# RC_Sheet1.net
KiCad netlist of a schematic drawn in Altium Designer
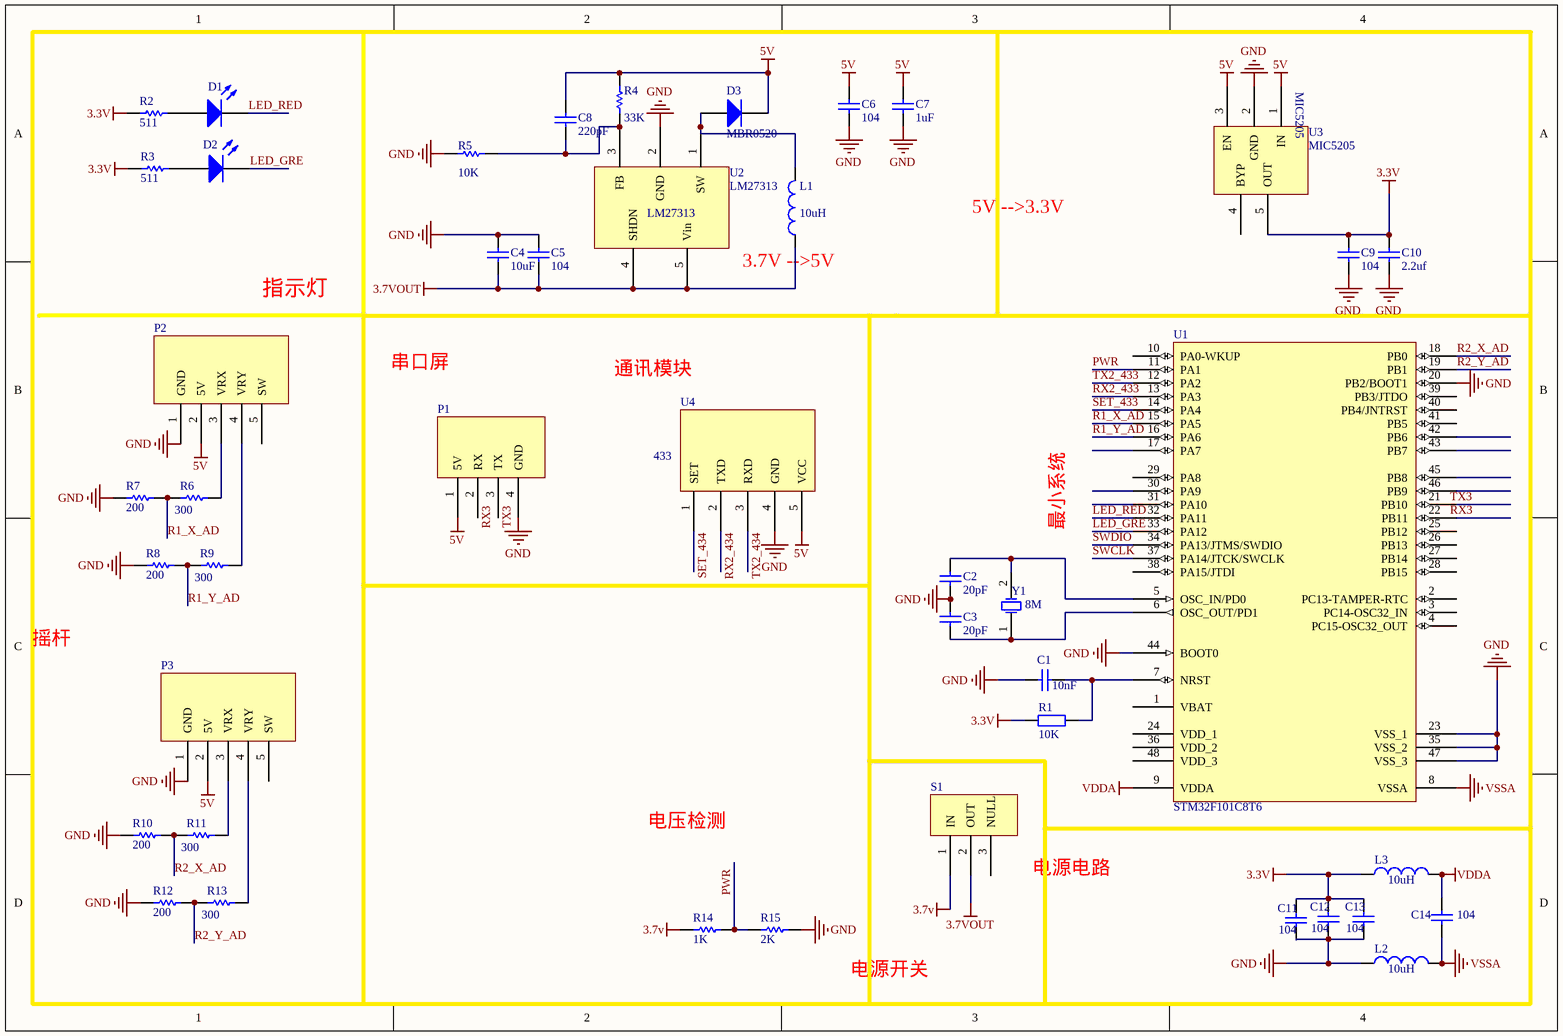
[diagram p0: RC_Sheet1.SchDoc]

(export (version "E")
  (design (tool "Eeschema 10.0.6"))
  (components
    (comp (ref "C1")
      (value "10nF")
      (footprint "0603-N-CAP")
      (description "Capacitor")
      (fields (field (name "Comment") "Cap") (field (name "PUBLISHER") "Altium Limited"))
      (libsource (lib "Miscellaneous Devices") (part "Cap"))
    )
    (comp (ref "C2")
      (value "20pF")
      (footprint "0603-N-CAP")
      (description "Capacitor")
      (fields (field (name "Comment") "Cap") (field (name "PUBLISHER") "Altium Limited"))
      (libsource (lib "Miscellaneous Devices") (part "Cap"))
    )
    (comp (ref "C3")
      (value "20pF")
      (footprint "0603-N-CAP")
      (description "Capacitor")
      (fields (field (name "Comment") "Cap") (field (name "PUBLISHER") "Altium Limited"))
      (libsource (lib "Miscellaneous Devices") (part "Cap"))
    )
    (comp (ref "C4")
      (value "10uF")
      (footprint "0603-N-CAP")
      (description "Capacitor")
      (fields (field (name "Comment") "Cap") (field (name "PUBLISHER") "Altium Limited"))
      (libsource (lib "Miscellaneous Devices") (part "Cap"))
    )
    (comp (ref "C5")
      (value "104")
      (footprint "0603-N-CAP")
      (description "Capacitor")
      (fields (field (name "Comment") "Cap") (field (name "PUBLISHER") "Altium Limited"))
      (libsource (lib "Miscellaneous Devices") (part "Cap"))
    )
    (comp (ref "C6")
      (value "104")
      (footprint "0603-N-CAP")
      (description "Capacitor")
      (fields (field (name "Comment") "Cap") (field (name "PUBLISHER") "Altium Limited"))
      (libsource (lib "Miscellaneous Devices") (part "Cap"))
    )
    (comp (ref "C7")
      (value "1uF")
      (footprint "0603-N-CAP")
      (description "Capacitor")
      (fields (field (name "Comment") "Cap") (field (name "PUBLISHER") "Altium Limited"))
      (libsource (lib "Miscellaneous Devices") (part "Cap"))
    )
    (comp (ref "C8")
      (value "220pF")
      (footprint "0603-N-CAP")
      (description "Capacitor")
      (fields (field (name "Comment") "Cap") (field (name "PUBLISHER") "Altium Limited"))
      (libsource (lib "Miscellaneous Devices") (part "Cap"))
    )
    (comp (ref "C9")
      (value "104")
      (footprint "0603-N-CAP")
      (description "Capacitor")
      (fields (field (name "Comment") "Cap") (field (name "PUBLISHER") "Altium Limited"))
      (libsource (lib "Miscellaneous Devices") (part "Cap"))
    )
    (comp (ref "C10")
      (value "2.2uf")
      (footprint "0603-N-CAP")
      (description "Capacitor")
      (fields (field (name "Comment") "Cap") (field (name "PUBLISHER") "Altium Limited"))
      (libsource (lib "Miscellaneous Devices") (part "Cap"))
    )
    (comp (ref "C11")
      (value "104")
      (footprint "0603-N-CAP")
      (description "Capacitor")
      (fields (field (name "Comment") "Cap") (field (name "PUBLISHER") "Altium Limited"))
      (libsource (lib "Miscellaneous Devices") (part "Cap"))
    )
    (comp (ref "C12")
      (value "104")
      (footprint "0603-N-CAP")
      (description "Capacitor")
      (fields (field (name "Comment") "Cap") (field (name "PUBLISHER") "Altium Limited"))
      (libsource (lib "Miscellaneous Devices") (part "Cap"))
    )
    (comp (ref "C13")
      (value "104")
      (footprint "0603-N-CAP")
      (description "Capacitor")
      (fields (field (name "Comment") "Cap") (field (name "PUBLISHER") "Altium Limited"))
      (libsource (lib "Miscellaneous Devices") (part "Cap"))
    )
    (comp (ref "C14")
      (value "104")
      (footprint "0603-N-CAP")
      (description "Capacitor")
      (fields (field (name "Comment") "Cap") (field (name "PUBLISHER") "Altium Limited"))
      (libsource (lib "Miscellaneous Devices") (part "Cap"))
    )
    (comp (ref "D1")
      (value "D2")
      (footprint "0603-N - LED-RED")
      (description "Typical BLUE SiC LED")
      (fields (field (name "PUBLISHER") "Altium Limited"))
      (libsource (lib "Miscellaneous Devices") (part "LED3"))
    )
    (comp (ref "D2")
      (value "D2")
      (footprint "0603-N - LED-RED")
      (description "Typical BLUE SiC LED")
      (fields (field (name "PUBLISHER") "Altium Limited"))
      (libsource (lib "Miscellaneous Devices") (part "LED3"))
    )
    (comp (ref "D3")
      (value "MBR0520")
      (footprint "425")
      (description "Default Diode")
      (fields (field (name "PUBLISHER") "Altium Limited"))
      (libsource (lib "Miscellaneous Devices") (part "Diode"))
    )
    (comp (ref "L1")
      (value "10uH")
      (footprint "0603-N - res")
      (description "Inductor")
      (fields (field (name "PUBLISHER") "Altium Limited"))
      (libsource (lib "Miscellaneous Devices") (part "Inductor"))
    )
    (comp (ref "L2")
      (value "10uH")
      (footprint "0603-N - res")
      (description "Inductor")
      (fields (field (name "PUBLISHER") "Altium Limited"))
      (libsource (lib "Miscellaneous Devices") (part "Inductor"))
    )
    (comp (ref "L3")
      (value "10uH")
      (footprint "0603-N - res")
      (description "Inductor")
      (fields (field (name "PUBLISHER") "Altium Limited"))
      (libsource (lib "Miscellaneous Devices") (part "Inductor"))
    )
    (comp (ref "P1") (value "串口屏") (libsource (lib "Schlib1") (part "串口屏")))
    (comp (ref "P2") (value "手柄") (libsource (lib "Schlib1") (part "手柄")))
    (comp (ref "P3") (value "手柄") (libsource (lib "Schlib1") (part "手柄")))
    (comp (ref "R1")
      (value "10K")
      (footprint "0603-N - res")
      (description "Resistor")
      (fields (field (name "Comment") "Res2") (field (name "PUBLISHER") "Altium Limited"))
      (libsource (lib "Miscellaneous Devices") (part "Res2"))
    )
    (comp (ref "R2")
      (value "511")
      (footprint "0603-N - res")
      (description "Resistor")
      (fields (field (name "Comment") "Res1") (field (name "PUBLISHER") "Altium Limited"))
      (libsource (lib "Miscellaneous Devices") (part "Res1"))
    )
    (comp (ref "R3")
      (value "511")
      (footprint "0603-N - res")
      (description "Resistor")
      (fields (field (name "Comment") "Res1") (field (name "PUBLISHER") "Altium Limited"))
      (libsource (lib "Miscellaneous Devices") (part "Res1"))
    )
    (comp (ref "R4")
      (value "33K")
      (footprint "0603-N - res")
      (description "Resistor")
      (fields (field (name "Comment") "Res1") (field (name "PUBLISHER") "Altium Limited"))
      (libsource (lib "Miscellaneous Devices") (part "Res1"))
    )
    (comp (ref "R5")
      (value "10K")
      (footprint "0603-N - res")
      (description "Resistor")
      (fields (field (name "Comment") "Res1") (field (name "PUBLISHER") "Altium Limited"))
      (libsource (lib "Miscellaneous Devices") (part "Res1"))
    )
    (comp (ref "R6")
      (value "300")
      (footprint "0603-N - res")
      (description "Resistor")
      (fields (field (name "Comment") "Res1") (field (name "PUBLISHER") "Altium Limited"))
      (libsource (lib "Miscellaneous Devices") (part "Res1"))
    )
    (comp (ref "R7")
      (value "200")
      (footprint "0603-N - res")
      (description "Resistor")
      (fields (field (name "Comment") "Res1") (field (name "PUBLISHER") "Altium Limited"))
      (libsource (lib "Miscellaneous Devices") (part "Res1"))
    )
    (comp (ref "R8")
      (value "200")
      (footprint "0603-N - res")
      (description "Resistor")
      (fields (field (name "Comment") "Res1") (field (name "PUBLISHER") "Altium Limited"))
      (libsource (lib "Miscellaneous Devices") (part "Res1"))
    )
    (comp (ref "R9")
      (value "300")
      (footprint "0603-N - res")
      (description "Resistor")
      (fields (field (name "Comment") "Res1") (field (name "PUBLISHER") "Altium Limited"))
      (libsource (lib "Miscellaneous Devices") (part "Res1"))
    )
    (comp (ref "R10")
      (value "200")
      (footprint "0603-N - res")
      (description "Resistor")
      (fields (field (name "Comment") "Res1") (field (name "PUBLISHER") "Altium Limited"))
      (libsource (lib "Miscellaneous Devices") (part "Res1"))
    )
    (comp (ref "R11")
      (value "300")
      (footprint "0603-N - res")
      (description "Resistor")
      (fields (field (name "Comment") "Res1") (field (name "PUBLISHER") "Altium Limited"))
      (libsource (lib "Miscellaneous Devices") (part "Res1"))
    )
    (comp (ref "R12")
      (value "200")
      (footprint "0603-N - res")
      (description "Resistor")
      (fields (field (name "Comment") "Res1") (field (name "PUBLISHER") "Altium Limited"))
      (libsource (lib "Miscellaneous Devices") (part "Res1"))
    )
    (comp (ref "R13")
      (value "300")
      (footprint "0603-N - res")
      (description "Resistor")
      (fields (field (name "Comment") "Res1") (field (name "PUBLISHER") "Altium Limited"))
      (libsource (lib "Miscellaneous Devices") (part "Res1"))
    )
    (comp (ref "R14")
      (value "1K")
      (footprint "0603-N - res")
      (description "Resistor")
      (fields (field (name "Comment") "Res1") (field (name "PUBLISHER") "Altium Limited"))
      (libsource (lib "Miscellaneous Devices") (part "Res1"))
    )
    (comp (ref "R15")
      (value "2K")
      (footprint "0603-N - res")
      (description "Resistor")
      (fields (field (name "Comment") "Res1") (field (name "PUBLISHER") "Altium Limited"))
      (libsource (lib "Miscellaneous Devices") (part "Res1"))
    )
    (comp (ref "S1") (value "switch") (footprint "SWITCH") (libsource (lib "Schlib1") (part "switch")))
    (comp (ref "U1")
      (value "STM32F101C8T6")
      (footprint "LQFP48_N")
      (description "STM32 ARM-based 32-bit MCU with 64 Kbytes Flash, 48-pin LQFP, Industrial Temperature")
      (fields (field (name "PUBLISHER") "Altium Limited"))
      (libsource (lib "ST Microcontroller 32-Bit STM32") (part "STM32F101C8T6"))
    )
    (comp (ref "U2")
      (value "LM27313")
      (footprint "SOT-23_5-001")
      (description "3.7V升压到5v")
      (libsource (lib "Schlib1") (part "LM27313"))
    )
    (comp (ref "U3")
      (value "MIC5205")
      (footprint "SOT-23_5-001")
      (description "5V降压到3.3V")
      (libsource (lib "Schlib1") (part "MIC5205"))
    )
    (comp (ref "U4")
      (value "433")
      (footprint "433")
      (description "通讯模块")
      (libsource (lib "Schlib1") (part "433"))
    )
    (comp (ref "Y1")
      (value "8M")
      (footprint "5032_")
      (description "Crystal Oscillator")
      (fields (field (name "PUBLISHER") "Altium Limited"))
      (libsource (lib "Miscellaneous Devices") (part "XTAL"))
    )
  )
  (nets
    (net (code "1") (name "/LED_GRE") (class "Default")
      (node (ref "D2") (pin "2") (pinfunction "K_2") (pintype "passive"))
      (node (ref "U1") (pin "33") (pinfunction "PA12_33") (pintype "bidirectional"))
    )
    (net (code "2") (name "/LED_RED") (class "Default")
      (node (ref "D1") (pin "2") (pinfunction "K_2") (pintype "passive"))
      (node (ref "U1") (pin "32") (pinfunction "PA11_32") (pintype "bidirectional"))
    )
    (net (code "3") (name "/PWR") (class "Default")
      (node (ref "R14") (pin "2") (pinfunction "2_2") (pintype "passive"))
      (node (ref "R15") (pin "1") (pinfunction "1_1") (pintype "passive"))
      (node (ref "U1") (pin "11") (pinfunction "PA1_11") (pintype "bidirectional"))
    )
    (net (code "4") (name "/R1_X_AD") (class "Default")
      (node (ref "R6") (pin "2") (pinfunction "2_2") (pintype "passive"))
      (node (ref "R7") (pin "1") (pinfunction "1_1") (pintype "passive"))
      (node (ref "U1") (pin "15") (pinfunction "PA5_15") (pintype "bidirectional"))
    )
    (net (code "5") (name "/R1_Y_AD") (class "Default")
      (node (ref "R8") (pin "1") (pinfunction "1_1") (pintype "passive"))
      (node (ref "R9") (pin "2") (pinfunction "2_2") (pintype "passive"))
      (node (ref "U1") (pin "16") (pinfunction "PA6_16") (pintype "bidirectional"))
    )
    (net (code "6") (name "/R2_X_AD") (class "Default")
      (node (ref "R10") (pin "1") (pinfunction "1_1") (pintype "passive"))
      (node (ref "R11") (pin "2") (pinfunction "2_2") (pintype "passive"))
      (node (ref "U1") (pin "18") (pinfunction "PB0_18") (pintype "bidirectional"))
    )
    (net (code "7") (name "/R2_Y_AD") (class "Default")
      (node (ref "R12") (pin "1") (pinfunction "1_1") (pintype "passive"))
      (node (ref "R13") (pin "2") (pinfunction "2_2") (pintype "passive"))
      (node (ref "U1") (pin "19") (pinfunction "PB1_19") (pintype "bidirectional"))
    )
    (net (code "8") (name "/RX2_433") (class "Default")
      (node (ref "U1") (pin "13") (pinfunction "PA3_13") (pintype "bidirectional"))
    )
    (net (code "9") (name "/RX2_434") (class "Default")
      (node (ref "U4") (pin "2") (pinfunction "TXD_2") (pintype "passive"))
    )
    (net (code "11") (name "/SET_433") (class "Default")
      (node (ref "U1") (pin "14") (pinfunction "PA4_14") (pintype "bidirectional"))
    )
    (net (code "12") (name "/SET_434") (class "Default")
      (node (ref "U4") (pin "1") (pinfunction "SET_1") (pintype "passive"))
    )
    (net (code "13") (name "/SWCLK") (class "Default")
      (node (ref "U1") (pin "37") (pinfunction "PA14/JTCK/SWCLK_37") (pintype "bidirectional"))
    )
    (net (code "14") (name "/SWDIO") (class "Default")
      (node (ref "U1") (pin "34") (pinfunction "PA13/JTMS/SWDIO_34") (pintype "bidirectional"))
    )
    (net (code "15") (name "/TX2_433") (class "Default")
      (node (ref "U1") (pin "12") (pinfunction "PA2_12") (pintype "bidirectional"))
    )
    (net (code "16") (name "/TX2_434") (class "Default")
      (node (ref "U4") (pin "3") (pinfunction "RXD_3") (pintype "passive"))
    )
    (net (code "18") (name "3.3V") (class "Default")
      (node (ref "C10") (pin "2") (pinfunction "2_2") (pintype "passive"))
      (node (ref "C11") (pin "2") (pinfunction "2_2") (pintype "passive"))
      (node (ref "C12") (pin "2") (pinfunction "2_2") (pintype "passive"))
      (node (ref "C13") (pin "2") (pinfunction "2_2") (pintype "passive"))
      (node (ref "C9") (pin "2") (pinfunction "2_2") (pintype "passive"))
      (node (ref "L3") (pin "1") (pinfunction "1_1") (pintype "passive"))
      (node (ref "R1") (pin "1") (pinfunction "1_1") (pintype "passive"))
      (node (ref "R2") (pin "2") (pinfunction "2_2") (pintype "passive"))
      (node (ref "R3") (pin "2") (pinfunction "2_2") (pintype "passive"))
      (node (ref "U3") (pin "5") (pinfunction "OUT_5") (pintype "passive"))
    )
    (net (code "19") (name "3.7VOUT") (class "Default")
      (node (ref "C4") (pin "1") (pinfunction "1_1") (pintype "passive"))
      (node (ref "C5") (pin "1") (pinfunction "1_1") (pintype "passive"))
      (node (ref "L1") (pin "1") (pinfunction "1_1") (pintype "passive"))
      (node (ref "S1") (pin "2") (pinfunction "OUT_2") (pintype "passive"))
      (node (ref "U2") (pin "4") (pinfunction "SHDN_4") (pintype "passive"))
      (node (ref "U2") (pin "5") (pinfunction "Vin_5") (pintype "passive"))
    )
    (net (code "20") (name "3.7v") (class "Default")
      (node (ref "R14") (pin "1") (pinfunction "1_1") (pintype "passive"))
      (node (ref "S1") (pin "1") (pinfunction "IN_1") (pintype "passive"))
    )
    (net (code "21") (name "5V") (class "Default")
      (node (ref "C6") (pin "2") (pinfunction "2_2") (pintype "passive"))
      (node (ref "C7") (pin "2") (pinfunction "2_2") (pintype "passive"))
      (node (ref "C8") (pin "2") (pinfunction "2_2") (pintype "passive"))
      (node (ref "D3") (pin "2") (pinfunction "K_2") (pintype "passive"))
      (node (ref "P1") (pin "1") (pinfunction "5V_1") (pintype "passive"))
      (node (ref "P2") (pin "2") (pinfunction "5V_2") (pintype "passive"))
      (node (ref "P3") (pin "2") (pinfunction "5V_2") (pintype "passive"))
      (node (ref "R4") (pin "2") (pinfunction "2_2") (pintype "passive"))
      (node (ref "U3") (pin "1") (pinfunction "IN_1") (pintype "passive"))
      (node (ref "U3") (pin "3") (pinfunction "EN_3") (pintype "passive"))
      (node (ref "U4") (pin "5") (pinfunction "VCC_5") (pintype "passive"))
    )
    (net (code "22") (name "GND") (class "Default")
      (node (ref "C1") (pin "1") (pinfunction "1_1") (pintype "passive"))
      (node (ref "C10") (pin "1") (pinfunction "1_1") (pintype "passive"))
      (node (ref "C11") (pin "1") (pinfunction "1_1") (pintype "passive"))
      (node (ref "C12") (pin "1") (pinfunction "1_1") (pintype "passive"))
      (node (ref "C13") (pin "1") (pinfunction "1_1") (pintype "passive"))
      (node (ref "C2") (pin "1") (pinfunction "1_1") (pintype "passive"))
      (node (ref "C3") (pin "2") (pinfunction "2_2") (pintype "passive"))
      (node (ref "C4") (pin "2") (pinfunction "2_2") (pintype "passive"))
      (node (ref "C5") (pin "2") (pinfunction "2_2") (pintype "passive"))
      (node (ref "C6") (pin "1") (pinfunction "1_1") (pintype "passive"))
      (node (ref "C7") (pin "1") (pinfunction "1_1") (pintype "passive"))
      (node (ref "C9") (pin "1") (pinfunction "1_1") (pintype "passive"))
      (node (ref "L2") (pin "1") (pinfunction "1_1") (pintype "passive"))
      (node (ref "P1") (pin "4") (pinfunction "GND_4") (pintype "passive"))
      (node (ref "P2") (pin "1") (pinfunction "GND_1") (pintype "passive"))
      (node (ref "P3") (pin "1") (pinfunction "GND_1") (pintype "passive"))
      (node (ref "R10") (pin "2") (pinfunction "2_2") (pintype "passive"))
      (node (ref "R12") (pin "2") (pinfunction "2_2") (pintype "passive"))
      (node (ref "R15") (pin "2") (pinfunction "2_2") (pintype "passive"))
      (node (ref "R5") (pin "1") (pinfunction "1_1") (pintype "passive"))
      (node (ref "R7") (pin "2") (pinfunction "2_2") (pintype "passive"))
      (node (ref "R8") (pin "2") (pinfunction "2_2") (pintype "passive"))
      (node (ref "U1") (pin "20") (pinfunction "PB2/BOOT1_20") (pintype "bidirectional"))
      (node (ref "U1") (pin "23") (pinfunction "VSS_1_23") (pintype "power_in"))
      (node (ref "U1") (pin "35") (pinfunction "VSS_2_35") (pintype "power_in"))
      (node (ref "U1") (pin "44") (pinfunction "BOOT0_44") (pintype "input"))
      (node (ref "U1") (pin "47") (pinfunction "VSS_3_47") (pintype "power_in"))
      (node (ref "U2") (pin "2") (pinfunction "GND_2") (pintype "passive"))
      (node (ref "U3") (pin "2") (pinfunction "GND_2") (pintype "passive"))
      (node (ref "U4") (pin "4") (pinfunction "GND_4") (pintype "passive"))
    )
    (net (code "23") (name "Net-(D1-A)") (class "Default")
      (node (ref "D1") (pin "1") (pinfunction "A_1") (pintype "passive"))
      (node (ref "R2") (pin "1") (pinfunction "1_1") (pintype "passive"))
    )
    (net (code "24") (name "Net-(D2-A)") (class "Default")
      (node (ref "D2") (pin "1") (pinfunction "A_1") (pintype "passive"))
      (node (ref "R3") (pin "1") (pinfunction "1_1") (pintype "passive"))
    )
    (net (code "25") (name "Net-(D3-A)") (class "Default")
      (node (ref "D3") (pin "1") (pinfunction "A_1") (pintype "passive"))
      (node (ref "L1") (pin "2") (pinfunction "2_2") (pintype "passive"))
      (node (ref "U2") (pin "1") (pinfunction "SW_1") (pintype "passive"))
    )
    (net (code "26") (name "Net-(P2-VRX)") (class "Default")
      (node (ref "P2") (pin "3") (pinfunction "VRX_3") (pintype "passive"))
      (node (ref "R6") (pin "1") (pinfunction "1_1") (pintype "passive"))
    )
    (net (code "27") (name "Net-(P2-VRY)") (class "Default")
      (node (ref "P2") (pin "4") (pinfunction "VRY_4") (pintype "passive"))
      (node (ref "R9") (pin "1") (pinfunction "1_1") (pintype "passive"))
    )
    (net (code "28") (name "Net-(P3-VRX)") (class "Default")
      (node (ref "P3") (pin "3") (pinfunction "VRX_3") (pintype "passive"))
      (node (ref "R11") (pin "1") (pinfunction "1_1") (pintype "passive"))
    )
    (net (code "29") (name "Net-(P3-VRY)") (class "Default")
      (node (ref "P3") (pin "4") (pinfunction "VRY_4") (pintype "passive"))
      (node (ref "R13") (pin "1") (pinfunction "1_1") (pintype "passive"))
    )
    (net (code "30") (name "Net-(U1-NRST)") (class "Default")
      (node (ref "C1") (pin "2") (pinfunction "2_2") (pintype "passive"))
      (node (ref "R1") (pin "2") (pinfunction "2_2") (pintype "passive"))
      (node (ref "U1") (pin "7") (pinfunction "NRST_7") (pintype "bidirectional"))
    )
    (net (code "31") (name "Net-(U1-OSC_IN{slash}PD0)") (class "Default")
      (node (ref "C2") (pin "2") (pinfunction "2_2") (pintype "passive"))
      (node (ref "U1") (pin "5") (pinfunction "OSC_IN/PD0_5") (pintype "input"))
      (node (ref "Y1") (pin "2") (pinfunction "OSC2_2") (pintype "passive"))
    )
    (net (code "32") (name "Net-(U1-OSC_OUT{slash}PD1)") (class "Default")
      (node (ref "C3") (pin "1") (pinfunction "1_1") (pintype "passive"))
      (node (ref "U1") (pin "6") (pinfunction "OSC_OUT/PD1_6") (pintype "output"))
      (node (ref "Y1") (pin "1") (pinfunction "OSC1_1") (pintype "passive"))
    )
    (net (code "33") (name "Net-(U2-FB)") (class "Default")
      (node (ref "C8") (pin "1") (pinfunction "1_1") (pintype "passive"))
      (node (ref "R4") (pin "1") (pinfunction "1_1") (pintype "passive"))
      (node (ref "R5") (pin "2") (pinfunction "2_2") (pintype "passive"))
      (node (ref "U2") (pin "3") (pinfunction "FB_3") (pintype "passive"))
    )
    (net (code "34") (name "VDDA") (class "Default")
      (node (ref "C14") (pin "2") (pinfunction "2_2") (pintype "passive"))
      (node (ref "L3") (pin "2") (pinfunction "2_2") (pintype "passive"))
      (node (ref "U1") (pin "9") (pinfunction "VDDA_9") (pintype "power_in"))
    )
    (net (code "35") (name "VSSA") (class "Default")
      (node (ref "C14") (pin "1") (pinfunction "1_1") (pintype "passive"))
      (node (ref "L2") (pin "2") (pinfunction "2_2") (pintype "passive"))
      (node (ref "U1") (pin "8") (pinfunction "VSSA_8") (pintype "power_in"))
    )
    (net (code "36") (name "unconnected-(P1-RX-Pad2)") (class "Default")
      (node (ref "P1") (pin "2") (pinfunction "RX_2") (pintype "passive"))
    )
    (net (code "37") (name "unconnected-(P1-TX-Pad3)") (class "Default")
      (node (ref "P1") (pin "3") (pinfunction "TX_3") (pintype "passive"))
    )
    (net (code "38") (name "unconnected-(P2-SW-Pad5)") (class "Default")
      (node (ref "P2") (pin "5") (pinfunction "SW_5") (pintype "passive"))
    )
    (net (code "39") (name "unconnected-(P3-SW-Pad5)") (class "Default")
      (node (ref "P3") (pin "5") (pinfunction "SW_5") (pintype "passive"))
    )
    (net (code "40") (name "unconnected-(S1-NULL-Pad3)") (class "Default")
      (node (ref "S1") (pin "3") (pinfunction "NULL_3") (pintype "passive"))
    )
    (net (code "41") (name "unconnected-(U1-PA0-WKUP-Pad10)") (class "Default")
      (node (ref "U1") (pin "10") (pinfunction "PA0-WKUP_10") (pintype "bidirectional"))
    )
    (net (code "42") (name "unconnected-(U1-PA7-Pad17)") (class "Default")
      (node (ref "U1") (pin "17") (pinfunction "PA7_17") (pintype "bidirectional"))
    )
    (net (code "43") (name "unconnected-(U1-PA8-Pad29)") (class "Default")
      (node (ref "U1") (pin "29") (pinfunction "PA8_29") (pintype "bidirectional"))
    )
    (net (code "44") (name "unconnected-(U1-PA9-Pad30)") (class "Default")
      (node (ref "U1") (pin "30") (pinfunction "PA9_30") (pintype "bidirectional"))
    )
    (net (code "45") (name "unconnected-(U1-PA10-Pad31)") (class "Default")
      (node (ref "U1") (pin "31") (pinfunction "PA10_31") (pintype "bidirectional"))
    )
    (net (code "46") (name "unconnected-(U1-PA15{slash}JTDI-Pad38)") (class "Default")
      (node (ref "U1") (pin "38") (pinfunction "PA15/JTDI_38") (pintype "bidirectional"))
    )
    (net (code "47") (name "unconnected-(U1-PB3{slash}JTDO-Pad39)") (class "Default")
      (node (ref "U1") (pin "39") (pinfunction "PB3/JTDO_39") (pintype "bidirectional"))
    )
    (net (code "48") (name "unconnected-(U1-PB4{slash}JNTRST-Pad40)") (class "Default")
      (node (ref "U1") (pin "40") (pinfunction "PB4/JNTRST_40") (pintype "bidirectional"))
    )
    (net (code "49") (name "unconnected-(U1-PB5-Pad41)") (class "Default")
      (node (ref "U1") (pin "41") (pinfunction "PB5_41") (pintype "bidirectional"))
    )
    (net (code "50") (name "unconnected-(U1-PB6-Pad42)") (class "Default")
      (node (ref "U1") (pin "42") (pinfunction "PB6_42") (pintype "bidirectional"))
    )
    (net (code "51") (name "unconnected-(U1-PB7-Pad43)") (class "Default")
      (node (ref "U1") (pin "43") (pinfunction "PB7_43") (pintype "bidirectional"))
    )
    (net (code "52") (name "unconnected-(U1-PB8-Pad45)") (class "Default")
      (node (ref "U1") (pin "45") (pinfunction "PB8_45") (pintype "bidirectional"))
    )
    (net (code "53") (name "unconnected-(U1-PB9-Pad46)") (class "Default")
      (node (ref "U1") (pin "46") (pinfunction "PB9_46") (pintype "bidirectional"))
    )
    (net (code "54") (name "unconnected-(U1-PB10-Pad21)") (class "Default")
      (node (ref "U1") (pin "21") (pinfunction "PB10_21") (pintype "bidirectional"))
    )
    (net (code "55") (name "unconnected-(U1-PB11-Pad22)") (class "Default")
      (node (ref "U1") (pin "22") (pinfunction "PB11_22") (pintype "bidirectional"))
    )
    (net (code "56") (name "unconnected-(U1-PB12-Pad25)") (class "Default")
      (node (ref "U1") (pin "25") (pinfunction "PB12_25") (pintype "bidirectional"))
    )
    (net (code "57") (name "unconnected-(U1-PB13-Pad26)") (class "Default")
      (node (ref "U1") (pin "26") (pinfunction "PB13_26") (pintype "bidirectional"))
    )
    (net (code "58") (name "unconnected-(U1-PB14-Pad27)") (class "Default")
      (node (ref "U1") (pin "27") (pinfunction "PB14_27") (pintype "bidirectional"))
    )
    (net (code "59") (name "unconnected-(U1-PB15-Pad28)") (class "Default")
      (node (ref "U1") (pin "28") (pinfunction "PB15_28") (pintype "bidirectional"))
    )
    (net (code "60") (name "unconnected-(U1-PC13-TAMPER-RTC-Pad2)") (class "Default")
      (node (ref "U1") (pin "2") (pinfunction "PC13-TAMPER-RTC_2") (pintype "bidirectional"))
    )
    (net (code "61") (name "unconnected-(U1-PC14-OSC32_IN-Pad3)") (class "Default")
      (node (ref "U1") (pin "3") (pinfunction "PC14-OSC32_IN_3") (pintype "bidirectional"))
    )
    (net (code "62") (name "unconnected-(U1-PC15-OSC32_OUT-Pad4)") (class "Default")
      (node (ref "U1") (pin "4") (pinfunction "PC15-OSC32_OUT_4") (pintype "bidirectional"))
    )
    (net (code "63") (name "unconnected-(U1-VBAT-Pad1)") (class "Default")
      (node (ref "U1") (pin "1") (pinfunction "VBAT_1") (pintype "power_in"))
    )
    (net (code "64") (name "unconnected-(U1-VDD_1-Pad24)") (class "Default")
      (node (ref "U1") (pin "24") (pinfunction "VDD_1_24") (pintype "power_in"))
    )
    (net (code "65") (name "unconnected-(U1-VDD_2-Pad36)") (class "Default")
      (node (ref "U1") (pin "36") (pinfunction "VDD_2_36") (pintype "power_in"))
    )
    (net (code "66") (name "unconnected-(U1-VDD_3-Pad48)") (class "Default")
      (node (ref "U1") (pin "48") (pinfunction "VDD_3_48") (pintype "power_in"))
    )
    (net (code "67") (name "unconnected-(U3-BYP-Pad4)") (class "Default")
      (node (ref "U3") (pin "4") (pinfunction "BYP_4") (pintype "passive"))
    )
  )
)
